# STl-Link-V10-final.net
KiCad netlist of a schematic drawn in EAGLE
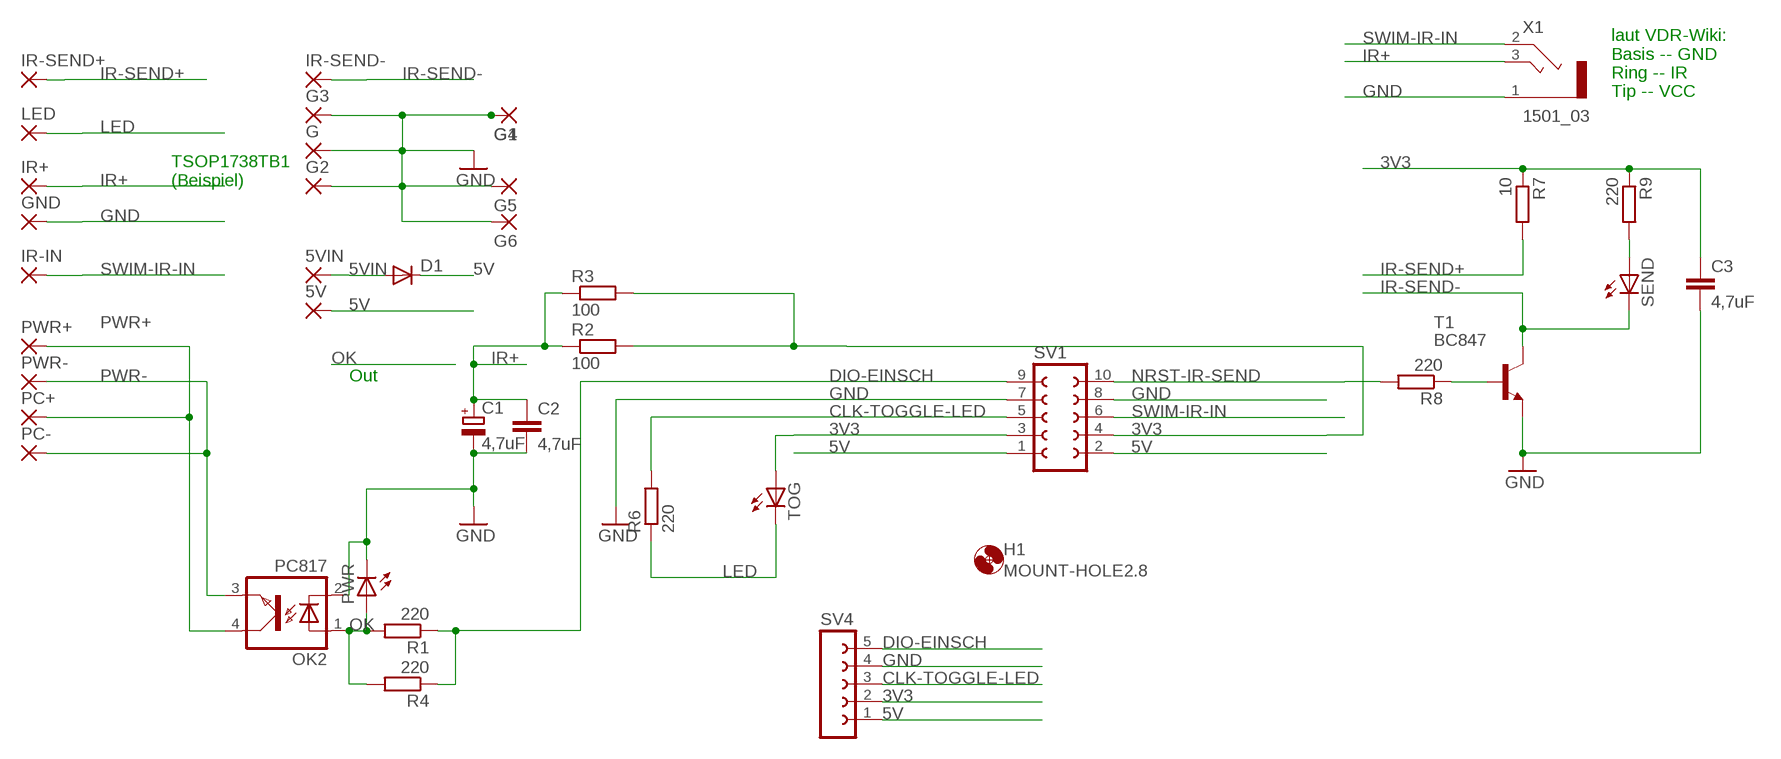
[diagram p0: schematic, sheet 1]

(export (version "E")
  (design (tool "Eeschema 10.0.6"))
  (components
    (comp (ref "5V")
      (value "SMD2")
      (footprint "eagle-import:SMD1,27-2,54")
      (libsource (lib "eagle-import") (part "SMD2"))
    )
    (comp (ref "5VIN")
      (value "SMD2")
      (footprint "eagle-import:SMD1,27-2,54")
      (libsource (lib "eagle-import") (part "SMD2"))
    )
    (comp (ref "C1")
      (value "4,7uF")
      (footprint "eagle-import:E1,8-4")
      (libsource (lib "eagle-import") (part "CPOL-EUE1.8-4"))
    )
    (comp (ref "C2")
      (value "4,7uF")
      (footprint "eagle-import:C1206K")
      (libsource (lib "eagle-import") (part "C-EUC1206K"))
    )
    (comp (ref "C3")
      (value "4,7uF")
      (footprint "eagle-import:C1206K")
      (libsource (lib "eagle-import") (part "C-EUC1206K"))
    )
    (comp (ref "D1")
      (value "DIODE-SOD123")
      (footprint "eagle-import:SOD123")
      (libsource (lib "eagle-import") (part "DIODE-SOD123"))
    )
    (comp (ref "G")
      (value "SMD2")
      (footprint "eagle-import:SMD1,27-2,54")
      (libsource (lib "eagle-import") (part "SMD2"))
    )
    (comp (ref "G1")
      (value "SMD2")
      (footprint "eagle-import:SMD1,27-2,54")
      (libsource (lib "eagle-import") (part "SMD2"))
    )
    (comp (ref "G2")
      (value "SMD2")
      (footprint "eagle-import:SMD1,27-2,54")
      (libsource (lib "eagle-import") (part "SMD2"))
    )
    (comp (ref "G3")
      (value "SMD2")
      (footprint "eagle-import:SMD1,27-2,54")
      (libsource (lib "eagle-import") (part "SMD2"))
    )
    (comp (ref "G4")
      (value "SMD2")
      (footprint "eagle-import:SMD1,27-2,54")
      (libsource (lib "eagle-import") (part "SMD2"))
    )
    (comp (ref "G5")
      (value "SMD2")
      (footprint "eagle-import:SMD1,27-2,54")
      (libsource (lib "eagle-import") (part "SMD2"))
    )
    (comp (ref "G6")
      (value "SMD2")
      (footprint "eagle-import:SMD1,27-2,54")
      (libsource (lib "eagle-import") (part "SMD2"))
    )
    (comp (ref "GND")
      (value "SMD2")
      (footprint "eagle-import:SMD1,27-2,54")
      (libsource (lib "eagle-import") (part "SMD2"))
    )
    (comp (ref "H1")
      (value "MOUNT-HOLE2.8")
      (footprint "eagle-import:2,8")
      (libsource (lib "eagle-import") (part "MOUNT-HOLE2.8"))
    )
    (comp (ref "IR+")
      (value "SMD2")
      (footprint "eagle-import:SMD1,27-2,54")
      (libsource (lib "eagle-import") (part "SMD2"))
    )
    (comp (ref "IR-IN")
      (value "SMD2")
      (footprint "eagle-import:SMD1,27-2,54")
      (libsource (lib "eagle-import") (part "SMD2"))
    )
    (comp (ref "IR-SEND+")
      (value "SMD2")
      (footprint "eagle-import:SMD1,27-2,54")
      (libsource (lib "eagle-import") (part "SMD2"))
    )
    (comp (ref "IR-SEND-")
      (value "SMD2")
      (footprint "eagle-import:SMD1,27-2,54")
      (libsource (lib "eagle-import") (part "SMD2"))
    )
    (comp (ref "LED")
      (value "SMD2")
      (footprint "eagle-import:SMD1,27-2,54")
      (libsource (lib "eagle-import") (part "SMD2"))
    )
    (comp (ref "OK2")
      (value "PC817")
      (footprint "eagle-import:DIL04")
      (fields (field (name "MPN") "PC817X4J000F"))
      (libsource (lib "eagle-import") (part "PC817"))
    )
    (comp (ref "PC+")
      (value "SMD2")
      (footprint "eagle-import:SMD1,27-2,54")
      (libsource (lib "eagle-import") (part "SMD2"))
    )
    (comp (ref "PC-")
      (value "SMD2")
      (footprint "eagle-import:SMD1,27-2,54")
      (libsource (lib "eagle-import") (part "SMD2"))
    )
    (comp (ref "PWR")
      (value "LEDCHIPLED_1206")
      (footprint "eagle-import:CHIPLED_1206")
      (libsource (lib "eagle-import") (part "LEDCHIPLED_1206"))
    )
    (comp (ref "PWR+")
      (value "SMD2")
      (footprint "eagle-import:SMD1,27-2,54")
      (libsource (lib "eagle-import") (part "SMD2"))
    )
    (comp (ref "PWR-")
      (value "SMD2")
      (footprint "eagle-import:SMD1,27-2,54")
      (libsource (lib "eagle-import") (part "SMD2"))
    )
    (comp (ref "R1")
      (value "220")
      (footprint "eagle-import:0204_7")
      (libsource (lib "eagle-import") (part "R-EU_0204/7"))
    )
    (comp (ref "R2")
      (value "100")
      (footprint "eagle-import:0204_7")
      (libsource (lib "eagle-import") (part "R-EU_0204/7"))
    )
    (comp (ref "R3")
      (value "100")
      (footprint "eagle-import:R0805W")
      (libsource (lib "eagle-import") (part "R-EU_R0805W"))
    )
    (comp (ref "R4")
      (value "220")
      (footprint "eagle-import:R0805W")
      (libsource (lib "eagle-import") (part "R-EU_R0805W"))
    )
    (comp (ref "R6")
      (value "220")
      (footprint "eagle-import:R0805W")
      (libsource (lib "eagle-import") (part "R-EU_R0805W"))
    )
    (comp (ref "R7")
      (value "10")
      (footprint "eagle-import:R0805W")
      (libsource (lib "eagle-import") (part "R-EU_R0805W"))
    )
    (comp (ref "R8")
      (value "220")
      (footprint "eagle-import:R0805W")
      (libsource (lib "eagle-import") (part "R-EU_R0805W"))
    )
    (comp (ref "R9")
      (value "220")
      (footprint "eagle-import:R0805W")
      (libsource (lib "eagle-import") (part "R-EU_R0805W"))
    )
    (comp (ref "SEND")
      (value "LEDCHIPLED_1206")
      (footprint "eagle-import:CHIPLED_1206")
      (libsource (lib "eagle-import") (part "LEDCHIPLED_1206"))
    )
    (comp (ref "SV1")
      (value "FE05-2")
      (footprint "eagle-import:FE05-2")
      (libsource (lib "eagle-import") (part "FE05-2"))
    )
    (comp (ref "SV4")
      (value "FE05-1")
      (footprint "eagle-import:FE05-1")
      (libsource (lib "eagle-import") (part "FE05-1"))
    )
    (comp (ref "T1")
      (value "BC847")
      (footprint "eagle-import:SOT23")
      (libsource (lib "eagle-import") (part "BC847"))
    )
    (comp (ref "TOG")
      (value "LEDCHIPLED_1206")
      (footprint "eagle-import:CHIPLED_1206")
      (libsource (lib "eagle-import") (part "LEDCHIPLED_1206"))
    )
    (comp (ref "X1")
      (value "1501_03")
      (footprint "eagle-import:1501_03")
      (libsource (lib "eagle-import") (part "1501_03"))
    )
  )
  (nets
    (net (code "1") (name "/3V3") (class "Default")
      (node (ref "C3") (pin "1") (pinfunction "1_1") (pintype "passive"))
      (node (ref "R2") (pin "2") (pinfunction "2_2") (pintype "passive"))
      (node (ref "R3") (pin "2") (pinfunction "2_2") (pintype "passive"))
      (node (ref "R7") (pin "1") (pinfunction "1_1") (pintype "passive"))
      (node (ref "R9") (pin "1") (pinfunction "1_1") (pintype "passive"))
      (node (ref "SV1") (pin "3") (pinfunction "3_3") (pintype "passive"))
      (node (ref "SV1") (pin "4") (pinfunction "4_4") (pintype "passive"))
      (node (ref "SV4") (pin "2") (pinfunction "2_2") (pintype "passive"))
      (node (ref "TOG") (pin "A") (pinfunction "A_A") (pintype "passive"))
    )
    (net (code "2") (name "/5V") (class "Default")
      (node (ref "5V") (pin "1") (pinfunction "P_1") (pintype "passive"))
      (node (ref "D1") (pin "C") (pinfunction "C_C") (pintype "passive"))
      (node (ref "SV1") (pin "1") (pinfunction "1_1") (pintype "passive"))
      (node (ref "SV1") (pin "2") (pinfunction "2_2") (pintype "passive"))
      (node (ref "SV4") (pin "1") (pinfunction "1_1") (pintype "passive"))
    )
    (net (code "3") (name "/5VIN") (class "Default")
      (node (ref "5VIN") (pin "1") (pinfunction "P_1") (pintype "passive"))
      (node (ref "D1") (pin "A") (pinfunction "A_A") (pintype "passive"))
    )
    (net (code "4") (name "/CLK-TOGGLE-LED") (class "Default")
      (node (ref "R6") (pin "2") (pinfunction "2_2") (pintype "passive"))
      (node (ref "SV1") (pin "5") (pinfunction "5_5") (pintype "passive"))
      (node (ref "SV4") (pin "3") (pinfunction "3_3") (pintype "passive"))
    )
    (net (code "5") (name "/DIO-EINSCH") (class "Default")
      (node (ref "R1") (pin "1") (pinfunction "1_1") (pintype "passive"))
      (node (ref "R4") (pin "1") (pinfunction "1_1") (pintype "passive"))
      (node (ref "SV1") (pin "9") (pinfunction "9_9") (pintype "passive"))
      (node (ref "SV4") (pin "5") (pinfunction "5_5") (pintype "passive"))
    )
    (net (code "6") (name "/IR+") (class "Default")
      (node (ref "C1") (pin "+") (pinfunction "+_+") (pintype "passive"))
      (node (ref "C2") (pin "1") (pinfunction "1_1") (pintype "passive"))
      (node (ref "IR+") (pin "1") (pinfunction "P_1") (pintype "passive"))
      (node (ref "R2") (pin "1") (pinfunction "1_1") (pintype "passive"))
      (node (ref "R3") (pin "1") (pinfunction "1_1") (pintype "passive"))
      (node (ref "X1") (pin "3") (pinfunction "3_3") (pintype "passive"))
    )
    (net (code "7") (name "/IR-SEND+") (class "Default")
      (node (ref "IR-SEND+") (pin "1") (pinfunction "P_1") (pintype "passive"))
      (node (ref "R7") (pin "2") (pinfunction "2_2") (pintype "passive"))
    )
    (net (code "8") (name "/IR-SEND-") (class "Default")
      (node (ref "IR-SEND-") (pin "1") (pinfunction "P_1") (pintype "passive"))
      (node (ref "SEND") (pin "C") (pinfunction "C_C") (pintype "passive"))
      (node (ref "T1") (pin "3") (pinfunction "C_3") (pintype "passive"))
    )
    (net (code "9") (name "/LED") (class "Default")
      (node (ref "LED") (pin "1") (pinfunction "P_1") (pintype "passive"))
      (node (ref "R6") (pin "1") (pinfunction "1_1") (pintype "passive"))
      (node (ref "TOG") (pin "C") (pinfunction "C_C") (pintype "passive"))
    )
    (net (code "10") (name "/NRST-IR-SEND") (class "Default")
      (node (ref "R8") (pin "2") (pinfunction "2_2") (pintype "passive"))
      (node (ref "SV1") (pin "10") (pinfunction "10_10") (pintype "passive"))
    )
    (net (code "11") (name "/OK") (class "Default")
      (node (ref "OK2") (pin "1") (pinfunction "A_1") (pintype "passive"))
      (node (ref "PWR") (pin "A") (pinfunction "A_A") (pintype "passive"))
      (node (ref "R1") (pin "2") (pinfunction "2_2") (pintype "passive"))
      (node (ref "R4") (pin "2") (pinfunction "2_2") (pintype "passive"))
    )
    (net (code "12") (name "/PWR+") (class "Default")
      (node (ref "OK2") (pin "4") (pinfunction "COL_4") (pintype "passive"))
      (node (ref "PC+") (pin "1") (pinfunction "P_1") (pintype "passive"))
      (node (ref "PWR+") (pin "1") (pinfunction "P_1") (pintype "passive"))
    )
    (net (code "13") (name "/PWR-") (class "Default")
      (node (ref "OK2") (pin "3") (pinfunction "EMIT_3") (pintype "passive"))
      (node (ref "PC-") (pin "1") (pinfunction "P_1") (pintype "passive"))
      (node (ref "PWR-") (pin "1") (pinfunction "P_1") (pintype "passive"))
    )
    (net (code "14") (name "/SWIM-IR-IN") (class "Default")
      (node (ref "IR-IN") (pin "1") (pinfunction "P_1") (pintype "passive"))
      (node (ref "SV1") (pin "6") (pinfunction "6_6") (pintype "passive"))
      (node (ref "X1") (pin "2") (pinfunction "2_2") (pintype "passive"))
    )
    (net (code "15") (name "GND") (class "Default")
      (node (ref "C1") (pin "-") (pinfunction "-_-") (pintype "passive"))
      (node (ref "C2") (pin "2") (pinfunction "2_2") (pintype "passive"))
      (node (ref "C3") (pin "2") (pinfunction "2_2") (pintype "passive"))
      (node (ref "G") (pin "1") (pinfunction "P_1") (pintype "passive"))
      (node (ref "G1") (pin "1") (pinfunction "P_1") (pintype "passive"))
      (node (ref "G2") (pin "1") (pinfunction "P_1") (pintype "passive"))
      (node (ref "G3") (pin "1") (pinfunction "P_1") (pintype "passive"))
      (node (ref "G4") (pin "1") (pinfunction "P_1") (pintype "passive"))
      (node (ref "G5") (pin "1") (pinfunction "P_1") (pintype "passive"))
      (node (ref "G6") (pin "1") (pinfunction "P_1") (pintype "passive"))
      (node (ref "GND") (pin "1") (pinfunction "P_1") (pintype "passive"))
      (node (ref "OK2") (pin "2") (pinfunction "C_2") (pintype "passive"))
      (node (ref "PWR") (pin "C") (pinfunction "C_C") (pintype "passive"))
      (node (ref "SV1") (pin "7") (pinfunction "7_7") (pintype "passive"))
      (node (ref "SV1") (pin "8") (pinfunction "8_8") (pintype "passive"))
      (node (ref "SV4") (pin "4") (pinfunction "4_4") (pintype "passive"))
      (node (ref "T1") (pin "2") (pinfunction "E_2") (pintype "passive"))
      (node (ref "X1") (pin "1") (pinfunction "1_1") (pintype "passive"))
    )
    (net (code "16") (name "Net-(R9-Pad2)") (class "Default")
      (node (ref "R9") (pin "2") (pinfunction "2_2") (pintype "passive"))
      (node (ref "SEND") (pin "A") (pinfunction "A_A") (pintype "passive"))
    )
    (net (code "17") (name "Net-(T1-B)") (class "Default")
      (node (ref "R8") (pin "1") (pinfunction "1_1") (pintype "passive"))
      (node (ref "T1") (pin "1") (pinfunction "B_1") (pintype "passive"))
    )
  )
)
